# OOBDROID_V1.net
KiCad netlist of a schematic drawn in EAGLE
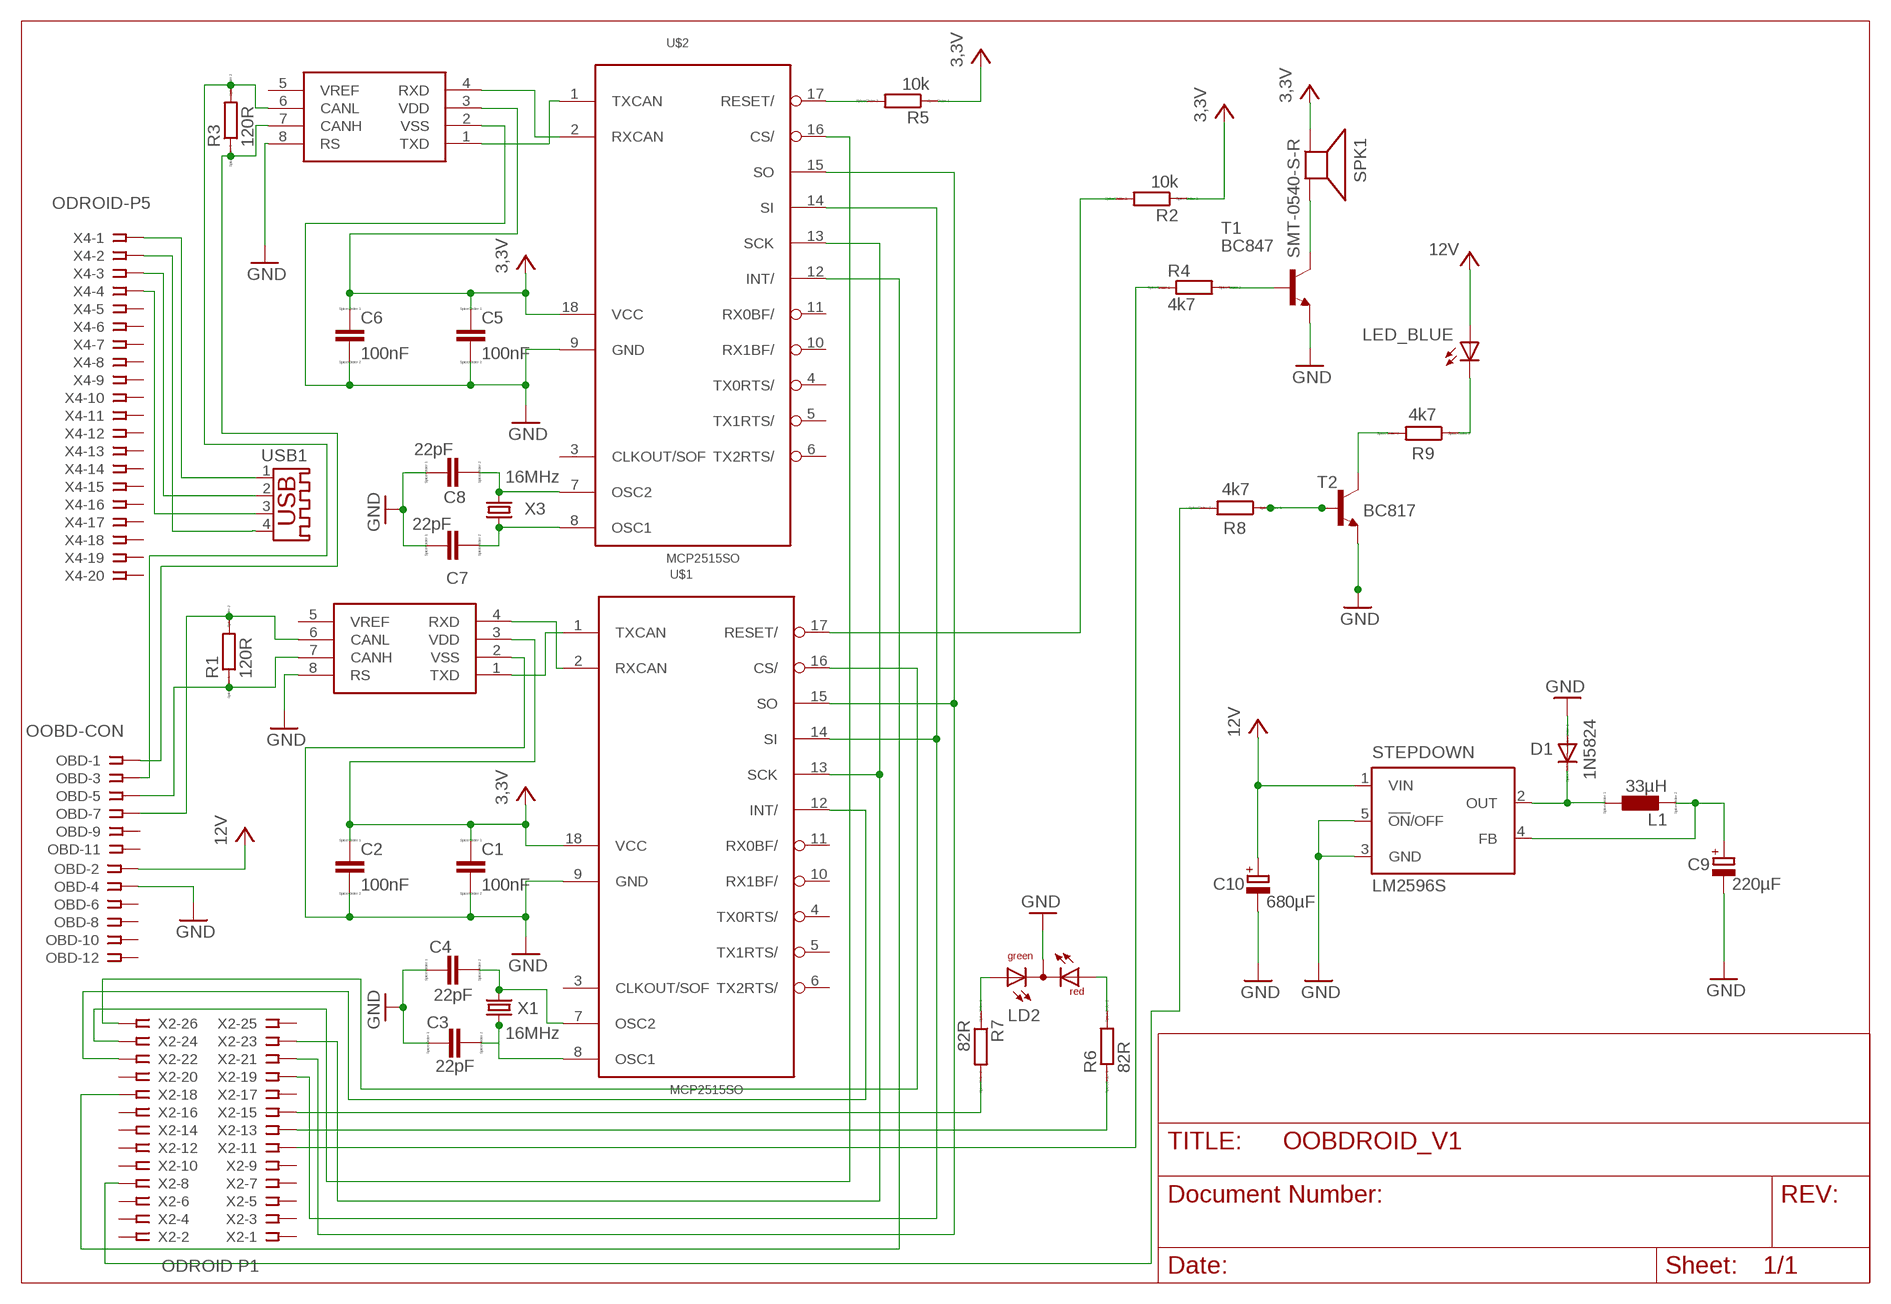
[diagram p0: schematic, sheet 1]

(export (version "E")
  (design (tool "Eeschema 10.0.6"))
  (components
    (comp (ref "C1")
      (value "100nF")
      (footprint "eagle-import:C0805")
      (libsource (lib "eagle-import") (part "C"))
    )
    (comp (ref "C2")
      (value "100nF")
      (footprint "eagle-import:C0805")
      (libsource (lib "eagle-import") (part "C"))
    )
    (comp (ref "C3")
      (value "22pF")
      (footprint "eagle-import:C0805")
      (libsource (lib "eagle-import") (part "C"))
    )
    (comp (ref "C4")
      (value "22pF")
      (footprint "eagle-import:C0805")
      (libsource (lib "eagle-import") (part "C"))
    )
    (comp (ref "C5")
      (value "100nF")
      (footprint "eagle-import:C0805")
      (libsource (lib "eagle-import") (part "C"))
    )
    (comp (ref "C6")
      (value "100nF")
      (footprint "eagle-import:C0805")
      (libsource (lib "eagle-import") (part "C"))
    )
    (comp (ref "C7")
      (value "22pF")
      (footprint "eagle-import:C0805")
      (libsource (lib "eagle-import") (part "C"))
    )
    (comp (ref "C8")
      (value "22pF")
      (footprint "eagle-import:C0805")
      (libsource (lib "eagle-import") (part "C"))
    )
    (comp (ref "C9")
      (value "220µF")
      (footprint "eagle-import:E1,8-4")
      (libsource (lib "eagle-import") (part "CPOL-EUE1.8-4"))
    )
    (comp (ref "C10")
      (value "680µF")
      (footprint "eagle-import:E1,8-4")
      (libsource (lib "eagle-import") (part "CPOL-EUE1.8-4"))
    )
    (comp (ref "D1")
      (value "1N5824")
      (footprint "eagle-import:DO214AA")
      (libsource (lib "eagle-import") (part "DIODE-DO214AA"))
    )
    (comp (ref "L1")
      (value "33µH")
      (footprint "eagle-import:L4532P")
      (libsource (lib "eagle-import") (part "LL4532P"))
    )
    (comp (ref "LD2")
      (value "DUOLED-RG-C")
      (footprint "eagle-import:DUOLED-C-5MM")
      (libsource (lib "eagle-import") (part "DUOLED-RG-C"))
    )
    (comp (ref "LED_BLUE")
      (value "LED5MM")
      (footprint "eagle-import:LED5MM")
      (libsource (lib "eagle-import") (part "LED5MM"))
    )
    (comp (ref "OBD")
      (value "OOBD-CON")
      (footprint "eagle-import:SSW-106-02-S-D")
      (fields (field (name "MPN") "SSW-106-02-S-D"))
      (libsource (lib "eagle-import") (part "SSW-106-02-S-D"))
    )
    (comp (ref "R1")
      (value "120R")
      (footprint "eagle-import:R0603")
      (libsource (lib "eagle-import") (part "RR0603"))
    )
    (comp (ref "R2")
      (value "10k")
      (footprint "eagle-import:R0603")
      (libsource (lib "eagle-import") (part "RR0603"))
    )
    (comp (ref "R3")
      (value "120R")
      (footprint "eagle-import:R0603")
      (libsource (lib "eagle-import") (part "RR0603"))
    )
    (comp (ref "R4")
      (value "4k7")
      (footprint "eagle-import:R0603")
      (libsource (lib "eagle-import") (part "RR0603"))
    )
    (comp (ref "R5")
      (value "10k")
      (footprint "eagle-import:R0603")
      (libsource (lib "eagle-import") (part "RR0603"))
    )
    (comp (ref "R6")
      (value "82R")
      (footprint "eagle-import:R0603")
      (libsource (lib "eagle-import") (part "RR0603"))
    )
    (comp (ref "R7")
      (value "82R")
      (footprint "eagle-import:R0603")
      (libsource (lib "eagle-import") (part "RR0603"))
    )
    (comp (ref "R8")
      (value "4k7")
      (footprint "eagle-import:R0603")
      (libsource (lib "eagle-import") (part "RR0603"))
    )
    (comp (ref "R9")
      (value "4k7")
      (footprint "eagle-import:R0603")
      (libsource (lib "eagle-import") (part "RR0603"))
    )
    (comp (ref "SPK1")
      (value "SMT-0540-S-R")
      (footprint "eagle-import:SMT-0540-S-R")
      (libsource (lib "eagle-import") (part "SMT-0540-S-R"))
    )
    (comp (ref "STEPDOWN")
      (value "LM2596S")
      (footprint "eagle-import:TO263-5")
      (fields (field (name "MF") "NATIONAL SEMICONDUCTOR") (field (name "MPN") "LM2596S-ADJ/NOPB"))
      (libsource (lib "eagle-import") (part "LM2596S"))
    )
    (comp (ref "T1")
      (value "BC847")
      (footprint "eagle-import:SOT23")
      (libsource (lib "eagle-import") (part "BC847"))
    )
    (comp (ref "T2")
      (value "BC817")
      (footprint "eagle-import:SOT23")
      (libsource (lib "eagle-import") (part "BC847"))
    )
    (comp (ref "U$1")
      (value "MCP2515SO")
      (footprint "eagle-import:SO18L")
      (libsource (lib "eagle-import") (part "MCP2515SO"))
    )
    (comp (ref "U$2")
      (value "MCP2515SO")
      (footprint "eagle-import:SO18L")
      (libsource (lib "eagle-import") (part "MCP2515SO"))
    )
    (comp (ref "U1")
      (value "MCP2551")
      (footprint "eagle-import:SO08")
      (libsource (lib "eagle-import") (part "MCP2551"))
    )
    (comp (ref "U2")
      (value "MCP2551")
      (footprint "eagle-import:SO08")
      (libsource (lib "eagle-import") (part "MCP2551"))
    )
    (comp (ref "USB1")
      (value "USB-A003")
      (footprint "eagle-import:USB-A003")
      (libsource (lib "eagle-import") (part "USB-A003"))
    )
    (comp (ref "X1")
      (value "16MHz")
      (footprint "eagle-import:HC49")
      (libsource (lib "eagle-import") (part "CRYSTALS-NOGND-HC49"))
    )
    (comp (ref "X2")
      (value "ODROID P1")
      (footprint "eagle-import:SSW-113-02-S-D")
      (fields (field (name "MPN") "SSW-113-02-S-D"))
      (libsource (lib "eagle-import") (part "SSW-113-02-S-D"))
    )
    (comp (ref "X3")
      (value "16MHz")
      (footprint "eagle-import:HC49")
      (libsource (lib "eagle-import") (part "CRYSTALS-NOGND-HC49"))
    )
    (comp (ref "X4")
      (value "ODROID-P5")
      (footprint "eagle-import:SSW-120-02-S-S")
      (fields (field (name "MPN") "SSW-120-02-S-S"))
      (libsource (lib "eagle-import") (part "SSW-120-02-S-S"))
    )
  )
  (nets
    (net (code "1") (name "12V") (class "Default")
      (node (ref "C1") (pin "1") (pinfunction "1_1") (pintype "passive"))
      (node (ref "C10") (pin "+") (pinfunction "+_+") (pintype "passive"))
      (node (ref "C2") (pin "1") (pinfunction "1_1") (pintype "passive"))
      (node (ref "C5") (pin "1") (pinfunction "1_1") (pintype "passive"))
      (node (ref "C6") (pin "1") (pinfunction "1_1") (pintype "passive"))
      (node (ref "LED_BLUE") (pin "A") (pinfunction "A_A") (pintype "passive"))
      (node (ref "OBD") (pin "2") (pinfunction "1_2") (pintype "passive"))
      (node (ref "R2") (pin "1") (pinfunction "1_1") (pintype "passive"))
      (node (ref "R5") (pin "1") (pinfunction "1_1") (pintype "passive"))
      (node (ref "SPK1") (pin "-") (pinfunction "+_-") (pintype "passive"))
      (node (ref "STEPDOWN") (pin "1") (pinfunction "VIN_1") (pintype "input"))
      (node (ref "U$1") (pin "18") (pinfunction "VCC_18") (pintype "power_in"))
      (node (ref "U$2") (pin "18") (pinfunction "VCC_18") (pintype "power_in"))
      (node (ref "U1") (pin "3") (pinfunction "VDD_3") (pintype "bidirectional"))
      (node (ref "U2") (pin "3") (pinfunction "VDD_3") (pintype "bidirectional"))
    )
    (net (code "2") (name "GND") (class "Default")
      (node (ref "C1") (pin "2") (pinfunction "2_2") (pintype "passive"))
      (node (ref "C10") (pin "-") (pinfunction "-_-") (pintype "passive"))
      (node (ref "C2") (pin "2") (pinfunction "2_2") (pintype "passive"))
      (node (ref "C3") (pin "1") (pinfunction "1_1") (pintype "passive"))
      (node (ref "C4") (pin "1") (pinfunction "1_1") (pintype "passive"))
      (node (ref "C5") (pin "2") (pinfunction "2_2") (pintype "passive"))
      (node (ref "C6") (pin "2") (pinfunction "2_2") (pintype "passive"))
      (node (ref "C7") (pin "1") (pinfunction "1_1") (pintype "passive"))
      (node (ref "C8") (pin "1") (pinfunction "1_1") (pintype "passive"))
      (node (ref "C9") (pin "-") (pinfunction "-_-") (pintype "passive"))
      (node (ref "D1") (pin "A") (pinfunction "A_A") (pintype "passive"))
      (node (ref "LD2") (pin "C") (pinfunction "C_C") (pintype "passive"))
      (node (ref "OBD") (pin "4") (pinfunction "1_4") (pintype "passive"))
      (node (ref "STEPDOWN") (pin "3") (pinfunction "GND_3") (pintype "power_in"))
      (node (ref "STEPDOWN") (pin "5") (pinfunction "~{ON}/OFF_5") (pintype "input"))
      (node (ref "T1") (pin "2") (pinfunction "E_2") (pintype "passive"))
      (node (ref "T2") (pin "2") (pinfunction "E_2") (pintype "passive"))
      (node (ref "U$1") (pin "9") (pinfunction "GND_9") (pintype "power_in"))
      (node (ref "U$2") (pin "9") (pinfunction "GND_9") (pintype "power_in"))
      (node (ref "U1") (pin "2") (pinfunction "VSS_2") (pintype "bidirectional"))
      (node (ref "U1") (pin "8") (pinfunction "RS_8") (pintype "bidirectional"))
      (node (ref "U2") (pin "2") (pinfunction "VSS_2") (pintype "bidirectional"))
      (node (ref "U2") (pin "8") (pinfunction "RS_8") (pintype "bidirectional"))
    )
    (net (code "3") (name "Net-(LD2-AG)") (class "Default")
      (node (ref "LD2") (pin "AX") (pinfunction "AG_AX") (pintype "passive"))
      (node (ref "R7") (pin "1") (pinfunction "1_1") (pintype "passive"))
    )
    (net (code "4") (name "Net-(LD2-PadAR)") (class "Default")
      (node (ref "LD2") (pin "AR") (pinfunction "AR_AR") (pintype "passive"))
      (node (ref "R6") (pin "2") (pinfunction "2_2") (pintype "passive"))
    )
    (net (code "5") (name "Net-(LED_BLUE-C)") (class "Default")
      (node (ref "LED_BLUE") (pin "K") (pinfunction "C_K") (pintype "passive"))
      (node (ref "R9") (pin "1") (pinfunction "1_1") (pintype "passive"))
    )
    (net (code "6") (name "Net-(OBDF-1)") (class "Default")
      (node (ref "OBD") (pin "3") (pinfunction "1_3") (pintype "passive"))
      (node (ref "R3") (pin "2") (pinfunction "2_2") (pintype "passive"))
      (node (ref "U2") (pin "6") (pinfunction "CANL_6") (pintype "bidirectional"))
    )
    (net (code "7") (name "Net-(OBDH-1)") (class "Default")
      (node (ref "OBD") (pin "5") (pinfunction "1_5") (pintype "passive"))
      (node (ref "R1") (pin "1") (pinfunction "1_1") (pintype "passive"))
      (node (ref "U1") (pin "7") (pinfunction "CANH_7") (pintype "bidirectional"))
    )
    (net (code "8") (name "Net-(OBDJ-1)") (class "Default")
      (node (ref "OBD") (pin "7") (pinfunction "1_7") (pintype "passive"))
      (node (ref "R1") (pin "2") (pinfunction "2_2") (pintype "passive"))
      (node (ref "U1") (pin "6") (pinfunction "CANL_6") (pintype "bidirectional"))
    )
    (net (code "9") (name "Net-(SPK1--)") (class "Default")
      (node (ref "SPK1") (pin "+") (pinfunction "-_+") (pintype "passive"))
      (node (ref "T1") (pin "3") (pinfunction "C_3") (pintype "passive"))
    )
    (net (code "10") (name "Net-(STEPDOWN-FB)") (class "Default")
      (node (ref "C9") (pin "+") (pinfunction "+_+") (pintype "passive"))
      (node (ref "L1") (pin "2") (pinfunction "2_2") (pintype "passive"))
      (node (ref "STEPDOWN") (pin "4") (pinfunction "FB_4") (pintype "input"))
    )
    (net (code "11") (name "Net-(STEPDOWN-OUT)") (class "Default")
      (node (ref "D1") (pin "C") (pinfunction "C_C") (pintype "passive"))
      (node (ref "L1") (pin "1") (pinfunction "1_1") (pintype "passive"))
      (node (ref "STEPDOWN") (pin "2") (pinfunction "OUT_2") (pintype "output"))
    )
    (net (code "12") (name "Net-(T1-B)") (class "Default")
      (node (ref "R4") (pin "2") (pinfunction "2_2") (pintype "passive"))
      (node (ref "T1") (pin "1") (pinfunction "B_1") (pintype "passive"))
    )
    (net (code "13") (name "Net-(T2-B)") (class "Default")
      (node (ref "R8") (pin "1") (pinfunction "1_1") (pintype "passive"))
      (node (ref "T2") (pin "1") (pinfunction "B_1") (pintype "passive"))
    )
    (net (code "14") (name "Net-(T2-C)") (class "Default")
      (node (ref "R9") (pin "2") (pinfunction "2_2") (pintype "passive"))
      (node (ref "T2") (pin "3") (pinfunction "C_3") (pintype "passive"))
    )
    (net (code "15") (name "Net-(U$1-CS{slash})") (class "Default")
      (node (ref "U$1") (pin "16") (pinfunction "CS/_16") (pintype "input"))
      (node (ref "X2") (pin "26") (pinfunction "1_26") (pintype "passive"))
    )
    (net (code "16") (name "Net-(U$1-INT{slash})") (class "Default")
      (node (ref "U$1") (pin "12") (pinfunction "INT/_12") (pintype "output"))
      (node (ref "X2") (pin "22") (pinfunction "1_22") (pintype "passive"))
    )
    (net (code "17") (name "Net-(U$1-OSC1)") (class "Default")
      (node (ref "C3") (pin "2") (pinfunction "2_2") (pintype "passive"))
      (node (ref "U$1") (pin "8") (pinfunction "OSC1_8") (pintype "bidirectional"))
      (node (ref "X1") (pin "1") (pinfunction "1_1") (pintype "passive"))
    )
    (net (code "18") (name "Net-(U$1-OSC2)") (class "Default")
      (node (ref "C4") (pin "2") (pinfunction "2_2") (pintype "passive"))
      (node (ref "U$1") (pin "7") (pinfunction "OSC2_7") (pintype "bidirectional"))
      (node (ref "X1") (pin "2") (pinfunction "2_2") (pintype "passive"))
    )
    (net (code "19") (name "Net-(U$1-RESET{slash})") (class "Default")
      (node (ref "R2") (pin "2") (pinfunction "2_2") (pintype "passive"))
      (node (ref "U$1") (pin "17") (pinfunction "RESET/_17") (pintype "input"))
    )
    (net (code "20") (name "Net-(U$1-RXCAN)") (class "Default")
      (node (ref "U$1") (pin "2") (pinfunction "RXCAN_2") (pintype "input"))
      (node (ref "U1") (pin "4") (pinfunction "RXD_4") (pintype "bidirectional"))
    )
    (net (code "21") (name "Net-(U$1-SCK)") (class "Default")
      (node (ref "U$1") (pin "13") (pinfunction "SCK_13") (pintype "input"))
      (node (ref "U$2") (pin "13") (pinfunction "SCK_13") (pintype "input"))
      (node (ref "X2") (pin "23") (pinfunction "1_23") (pintype "passive"))
    )
    (net (code "22") (name "Net-(U$1-SI)") (class "Default")
      (node (ref "U$1") (pin "14") (pinfunction "SI_14") (pintype "input"))
      (node (ref "U$2") (pin "14") (pinfunction "SI_14") (pintype "input"))
      (node (ref "X2") (pin "19") (pinfunction "1_19") (pintype "passive"))
    )
    (net (code "23") (name "Net-(U$1-SO)") (class "Default")
      (node (ref "U$1") (pin "15") (pinfunction "SO_15") (pintype "output"))
      (node (ref "U$2") (pin "15") (pinfunction "SO_15") (pintype "output"))
      (node (ref "X2") (pin "21") (pinfunction "1_21") (pintype "passive"))
    )
    (net (code "24") (name "Net-(U$1-TXCAN)") (class "Default")
      (node (ref "U$1") (pin "1") (pinfunction "TXCAN_1") (pintype "output"))
      (node (ref "U1") (pin "1") (pinfunction "TXD_1") (pintype "bidirectional"))
    )
    (net (code "25") (name "Net-(U$2-CS{slash})") (class "Default")
      (node (ref "U$2") (pin "16") (pinfunction "CS/_16") (pintype "input"))
      (node (ref "X2") (pin "24") (pinfunction "1_24") (pintype "passive"))
    )
    (net (code "26") (name "Net-(U$2-INT{slash})") (class "Default")
      (node (ref "U$2") (pin "12") (pinfunction "INT/_12") (pintype "output"))
      (node (ref "X2") (pin "18") (pinfunction "1_18") (pintype "passive"))
    )
    (net (code "27") (name "Net-(U$2-OSC1)") (class "Default")
      (node (ref "C7") (pin "2") (pinfunction "2_2") (pintype "passive"))
      (node (ref "U$2") (pin "8") (pinfunction "OSC1_8") (pintype "bidirectional"))
      (node (ref "X3") (pin "1") (pinfunction "1_1") (pintype "passive"))
    )
    (net (code "28") (name "Net-(U$2-OSC2)") (class "Default")
      (node (ref "C8") (pin "2") (pinfunction "2_2") (pintype "passive"))
      (node (ref "U$2") (pin "7") (pinfunction "OSC2_7") (pintype "bidirectional"))
      (node (ref "X3") (pin "2") (pinfunction "2_2") (pintype "passive"))
    )
    (net (code "29") (name "Net-(U$2-RESET{slash})") (class "Default")
      (node (ref "R5") (pin "2") (pinfunction "2_2") (pintype "passive"))
      (node (ref "U$2") (pin "17") (pinfunction "RESET/_17") (pintype "input"))
    )
    (net (code "30") (name "Net-(U$2-RXCAN)") (class "Default")
      (node (ref "U$2") (pin "2") (pinfunction "RXCAN_2") (pintype "input"))
      (node (ref "U2") (pin "4") (pinfunction "RXD_4") (pintype "bidirectional"))
    )
    (net (code "31") (name "Net-(U$2-TXCAN)") (class "Default")
      (node (ref "U$2") (pin "1") (pinfunction "TXCAN_1") (pintype "output"))
      (node (ref "U2") (pin "1") (pinfunction "TXD_1") (pintype "bidirectional"))
    )
    (net (code "32") (name "Net-(U2-CANH)") (class "Default")
      (node (ref "OBD") (pin "1") (pinfunction "1_1") (pintype "passive"))
      (node (ref "R3") (pin "1") (pinfunction "1_1") (pintype "passive"))
      (node (ref "U2") (pin "7") (pinfunction "CANH_7") (pintype "bidirectional"))
    )
    (net (code "33") (name "Net-(USB1-Pad1)") (class "Default")
      (node (ref "USB1") (pin "1") (pinfunction "1_1") (pintype "passive"))
      (node (ref "X4") (pin "1") (pinfunction "1_1") (pintype "passive"))
    )
    (net (code "34") (name "Net-(X2C-1)") (class "Default")
      (node (ref "R4") (pin "1") (pinfunction "1_1") (pintype "passive"))
      (node (ref "X2") (pin "11") (pinfunction "1_11") (pintype "passive"))
    )
    (net (code "35") (name "Net-(X2E-1)") (class "Default")
      (node (ref "R6") (pin "1") (pinfunction "1_1") (pintype "passive"))
      (node (ref "X2") (pin "13") (pinfunction "1_13") (pintype "passive"))
    )
    (net (code "36") (name "Net-(X2G-1)") (class "Default")
      (node (ref "R7") (pin "2") (pinfunction "2_2") (pintype "passive"))
      (node (ref "X2") (pin "15") (pinfunction "1_15") (pintype "passive"))
    )
    (net (code "37") (name "Net-(X2Y-1)") (class "Default")
      (node (ref "R8") (pin "2") (pinfunction "2_2") (pintype "passive"))
      (node (ref "X2") (pin "8") (pinfunction "1_8") (pintype "passive"))
    )
    (net (code "38") (name "Net-(X4L-1)") (class "Default")
      (node (ref "USB1") (pin "4") (pinfunction "4_4") (pintype "passive"))
      (node (ref "X4") (pin "2") (pinfunction "1_2") (pintype "passive"))
    )
    (net (code "39") (name "Net-(X4N-1)") (class "Default")
      (node (ref "USB1") (pin "2") (pinfunction "2_2") (pintype "passive"))
      (node (ref "X4") (pin "3") (pinfunction "1_3") (pintype "passive"))
    )
    (net (code "40") (name "Net-(X4O-1)") (class "Default")
      (node (ref "USB1") (pin "3") (pinfunction "3_3") (pintype "passive"))
      (node (ref "X4") (pin "4") (pinfunction "1_4") (pintype "passive"))
    )
    (net (code "41") (name "unconnected-(OBDB-1-Pad10)") (class "Default")
      (node (ref "OBD") (pin "10") (pinfunction "1_10") (pintype "passive"))
    )
    (net (code "42") (name "unconnected-(OBDC-1-Pad11)") (class "Default")
      (node (ref "OBD") (pin "11") (pinfunction "1_11") (pintype "passive"))
    )
    (net (code "43") (name "unconnected-(OBDD-1-Pad12)") (class "Default")
      (node (ref "OBD") (pin "12") (pinfunction "1_12") (pintype "passive"))
    )
    (net (code "44") (name "unconnected-(OBDI-1-Pad6)") (class "Default")
      (node (ref "OBD") (pin "6") (pinfunction "1_6") (pintype "passive"))
    )
    (net (code "45") (name "unconnected-(OBDK-1-Pad8)") (class "Default")
      (node (ref "OBD") (pin "8") (pinfunction "1_8") (pintype "passive"))
    )
    (net (code "46") (name "unconnected-(OBDL-1-Pad9)") (class "Default")
      (node (ref "OBD") (pin "9") (pinfunction "1_9") (pintype "passive"))
    )
    (net (code "47") (name "unconnected-(U$1-CLKOUT{slash}SOF-Pad3)") (class "Default")
      (node (ref "U$1") (pin "3") (pinfunction "CLKOUT/SOF_3") (pintype "bidirectional"))
    )
    (net (code "48") (name "unconnected-(U$1-RX0BF{slash}-Pad11)") (class "Default")
      (node (ref "U$1") (pin "11") (pinfunction "RX0BF/_11") (pintype "bidirectional"))
    )
    (net (code "49") (name "unconnected-(U$1-RX1BF{slash}-Pad10)") (class "Default")
      (node (ref "U$1") (pin "10") (pinfunction "RX1BF/_10") (pintype "bidirectional"))
    )
    (net (code "50") (name "unconnected-(U$1-TX0RTS{slash}-Pad4)") (class "Default")
      (node (ref "U$1") (pin "4") (pinfunction "TX0RTS/_4") (pintype "bidirectional"))
    )
    (net (code "51") (name "unconnected-(U$1-TX1RTS{slash}-Pad5)") (class "Default")
      (node (ref "U$1") (pin "5") (pinfunction "TX1RTS/_5") (pintype "bidirectional"))
    )
    (net (code "52") (name "unconnected-(U$1-TX2RTS{slash}-Pad6)") (class "Default")
      (node (ref "U$1") (pin "6") (pinfunction "TX2RTS/_6") (pintype "bidirectional"))
    )
    (net (code "53") (name "unconnected-(U$2-CLKOUT{slash}SOF-Pad3)") (class "Default")
      (node (ref "U$2") (pin "3") (pinfunction "CLKOUT/SOF_3") (pintype "bidirectional"))
    )
    (net (code "54") (name "unconnected-(U$2-RX0BF{slash}-Pad11)") (class "Default")
      (node (ref "U$2") (pin "11") (pinfunction "RX0BF/_11") (pintype "bidirectional"))
    )
    (net (code "55") (name "unconnected-(U$2-RX1BF{slash}-Pad10)") (class "Default")
      (node (ref "U$2") (pin "10") (pinfunction "RX1BF/_10") (pintype "bidirectional"))
    )
    (net (code "56") (name "unconnected-(U$2-TX0RTS{slash}-Pad4)") (class "Default")
      (node (ref "U$2") (pin "4") (pinfunction "TX0RTS/_4") (pintype "bidirectional"))
    )
    (net (code "57") (name "unconnected-(U$2-TX1RTS{slash}-Pad5)") (class "Default")
      (node (ref "U$2") (pin "5") (pinfunction "TX1RTS/_5") (pintype "bidirectional"))
    )
    (net (code "58") (name "unconnected-(U$2-TX2RTS{slash}-Pad6)") (class "Default")
      (node (ref "U$2") (pin "6") (pinfunction "TX2RTS/_6") (pintype "bidirectional"))
    )
    (net (code "59") (name "unconnected-(U1-VREF-Pad5)") (class "Default")
      (node (ref "U1") (pin "5") (pinfunction "VREF_5") (pintype "bidirectional"))
    )
    (net (code "60") (name "unconnected-(U2-VREF-Pad5)") (class "Default")
      (node (ref "U2") (pin "5") (pinfunction "VREF_5") (pintype "bidirectional"))
    )
    (net (code "61") (name "unconnected-(X2-Pad1)") (class "Default")
      (node (ref "X2") (pin "1") (pinfunction "1_1") (pintype "passive"))
    )
    (net (code "62") (name "unconnected-(X2B-1-Pad10)") (class "Default")
      (node (ref "X2") (pin "10") (pinfunction "1_10") (pintype "passive"))
    )
    (net (code "63") (name "unconnected-(X2D-1-Pad12)") (class "Default")
      (node (ref "X2") (pin "12") (pinfunction "1_12") (pintype "passive"))
    )
    (net (code "64") (name "unconnected-(X2F-1-Pad14)") (class "Default")
      (node (ref "X2") (pin "14") (pinfunction "1_14") (pintype "passive"))
    )
    (net (code "65") (name "unconnected-(X2H-1-Pad16)") (class "Default")
      (node (ref "X2") (pin "16") (pinfunction "1_16") (pintype "passive"))
    )
    (net (code "66") (name "unconnected-(X2I-1-Pad17)") (class "Default")
      (node (ref "X2") (pin "17") (pinfunction "1_17") (pintype "passive"))
    )
    (net (code "67") (name "unconnected-(X2L-1-Pad2)") (class "Default")
      (node (ref "X2") (pin "2") (pinfunction "1_2") (pintype "passive"))
    )
    (net (code "68") (name "unconnected-(X2M-1-Pad20)") (class "Default")
      (node (ref "X2") (pin "20") (pinfunction "1_20") (pintype "passive"))
    )
    (net (code "69") (name "unconnected-(X2R-1-Pad25)") (class "Default")
      (node (ref "X2") (pin "25") (pinfunction "1_25") (pintype "passive"))
    )
    (net (code "70") (name "unconnected-(X2T-1-Pad3)") (class "Default")
      (node (ref "X2") (pin "3") (pinfunction "1_3") (pintype "passive"))
    )
    (net (code "71") (name "unconnected-(X2U-1-Pad4)") (class "Default")
      (node (ref "X2") (pin "4") (pinfunction "1_4") (pintype "passive"))
    )
    (net (code "72") (name "unconnected-(X2V-1-Pad5)") (class "Default")
      (node (ref "X2") (pin "5") (pinfunction "1_5") (pintype "passive"))
    )
    (net (code "73") (name "unconnected-(X2W-1-Pad6)") (class "Default")
      (node (ref "X2") (pin "6") (pinfunction "1_6") (pintype "passive"))
    )
    (net (code "74") (name "unconnected-(X2X-1-Pad7)") (class "Default")
      (node (ref "X2") (pin "7") (pinfunction "1_7") (pintype "passive"))
    )
    (net (code "75") (name "unconnected-(X2Z-1-Pad9)") (class "Default")
      (node (ref "X2") (pin "9") (pinfunction "1_9") (pintype "passive"))
    )
    (net (code "76") (name "unconnected-(X4B-1-Pad10)") (class "Default")
      (node (ref "X4") (pin "10") (pinfunction "1_10") (pintype "passive"))
    )
    (net (code "77") (name "unconnected-(X4C-1-Pad11)") (class "Default")
      (node (ref "X4") (pin "11") (pinfunction "1_11") (pintype "passive"))
    )
    (net (code "78") (name "unconnected-(X4D-1-Pad12)") (class "Default")
      (node (ref "X4") (pin "12") (pinfunction "1_12") (pintype "passive"))
    )
    (net (code "79") (name "unconnected-(X4E-1-Pad13)") (class "Default")
      (node (ref "X4") (pin "13") (pinfunction "1_13") (pintype "passive"))
    )
    (net (code "80") (name "unconnected-(X4F-1-Pad14)") (class "Default")
      (node (ref "X4") (pin "14") (pinfunction "1_14") (pintype "passive"))
    )
    (net (code "81") (name "unconnected-(X4G-1-Pad15)") (class "Default")
      (node (ref "X4") (pin "15") (pinfunction "1_15") (pintype "passive"))
    )
    (net (code "82") (name "unconnected-(X4H-1-Pad16)") (class "Default")
      (node (ref "X4") (pin "16") (pinfunction "1_16") (pintype "passive"))
    )
    (net (code "83") (name "unconnected-(X4I-1-Pad17)") (class "Default")
      (node (ref "X4") (pin "17") (pinfunction "1_17") (pintype "passive"))
    )
    (net (code "84") (name "unconnected-(X4J-1-Pad18)") (class "Default")
      (node (ref "X4") (pin "18") (pinfunction "1_18") (pintype "passive"))
    )
    (net (code "85") (name "unconnected-(X4K-1-Pad19)") (class "Default")
      (node (ref "X4") (pin "19") (pinfunction "1_19") (pintype "passive"))
    )
    (net (code "86") (name "unconnected-(X4M-1-Pad20)") (class "Default")
      (node (ref "X4") (pin "20") (pinfunction "1_20") (pintype "passive"))
    )
    (net (code "87") (name "unconnected-(X4P-1-Pad5)") (class "Default")
      (node (ref "X4") (pin "5") (pinfunction "1_5") (pintype "passive"))
    )
    (net (code "88") (name "unconnected-(X4Q-1-Pad6)") (class "Default")
      (node (ref "X4") (pin "6") (pinfunction "1_6") (pintype "passive"))
    )
    (net (code "89") (name "unconnected-(X4R-1-Pad7)") (class "Default")
      (node (ref "X4") (pin "7") (pinfunction "1_7") (pintype "passive"))
    )
    (net (code "90") (name "unconnected-(X4S-1-Pad8)") (class "Default")
      (node (ref "X4") (pin "8") (pinfunction "1_8") (pintype "passive"))
    )
    (net (code "91") (name "unconnected-(X4T-1-Pad9)") (class "Default")
      (node (ref "X4") (pin "9") (pinfunction "1_9") (pintype "passive"))
    )
  )
)
